# Power_3_3_module.net
KiCad netlist of a schematic drawn in Altium Designer
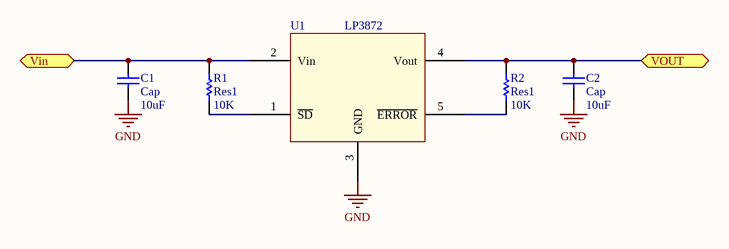
[diagram p0: Power_3_3_module.SchDoc]

(export (version "E")
  (design (tool "Eeschema 10.0.6"))
  (components
    (comp (ref "C1")
      (value "Cap")
      (footprint "RESC6332")
      (description "Capacitor")
      (fields (field (name "ALTIUM_VALUE") "10uF") (field (name "PUBLISHER") "Altium Limited"))
      (libsource (lib "Miscellaneous Devices") (part "Cap"))
    )
    (comp (ref "C2")
      (value "Cap")
      (footprint "RESC6332")
      (description "Capacitor")
      (fields (field (name "ALTIUM_VALUE") "10uF") (field (name "PUBLISHER") "Altium Limited"))
      (libsource (lib "Miscellaneous Devices") (part "Cap"))
    )
    (comp (ref "R1")
      (value "Res1")
      (footprint "RESC6332")
      (description "Resistor")
      (fields (field (name "ALTIUM_VALUE") "10K") (field (name "PUBLISHER") "Altium Limited"))
      (libsource (lib "Miscellaneous Devices") (part "Res1"))
    )
    (comp (ref "R2")
      (value "Res1")
      (footprint "RESC6332")
      (description "Resistor")
      (fields (field (name "ALTIUM_VALUE") "10K") (field (name "PUBLISHER") "Altium Limited"))
      (libsource (lib "Miscellaneous Devices") (part "Res1"))
    )
    (comp (ref "U1")
      (value "LP3872")
      (footprint "SOT150P700X180-5N")
      (libsource (lib "Motor_parts_sch_lib") (part "LP3872"))
    )
  )
  (nets
    (net (code "1") (name "/VOUT") (class "Default")
      (node (ref "C2") (pin "1") (pinfunction "1_1") (pintype "passive"))
      (node (ref "R2") (pin "2") (pinfunction "2_2") (pintype "passive"))
      (node (ref "U1") (pin "4") (pinfunction "Vout_4") (pintype "passive"))
    )
    (net (code "2") (name "/Vin") (class "Default")
      (node (ref "C1") (pin "1") (pinfunction "1_1") (pintype "passive"))
      (node (ref "R1") (pin "2") (pinfunction "2_2") (pintype "passive"))
      (node (ref "U1") (pin "2") (pinfunction "Vin_2") (pintype "passive"))
    )
    (net (code "3") (name "GND") (class "Default")
      (node (ref "C1") (pin "2") (pinfunction "2_2") (pintype "passive"))
      (node (ref "C2") (pin "2") (pinfunction "2_2") (pintype "passive"))
      (node (ref "U1") (pin "3") (pinfunction "GND_3") (pintype "passive"))
    )
    (net (code "4") (name "Net-(U1-~{ERROR})") (class "Default")
      (node (ref "R2") (pin "1") (pinfunction "1_1") (pintype "passive"))
      (node (ref "U1") (pin "5") (pinfunction "~{ERROR}_5") (pintype "passive"))
    )
    (net (code "5") (name "Net-(U1-~{SD})") (class "Default")
      (node (ref "R1") (pin "1") (pinfunction "1_1") (pintype "passive"))
      (node (ref "U1") (pin "1") (pinfunction "~{SD}_1") (pintype "passive"))
    )
  )
)
